# usbasp.net
KiCad netlist of a schematic drawn in EAGLE
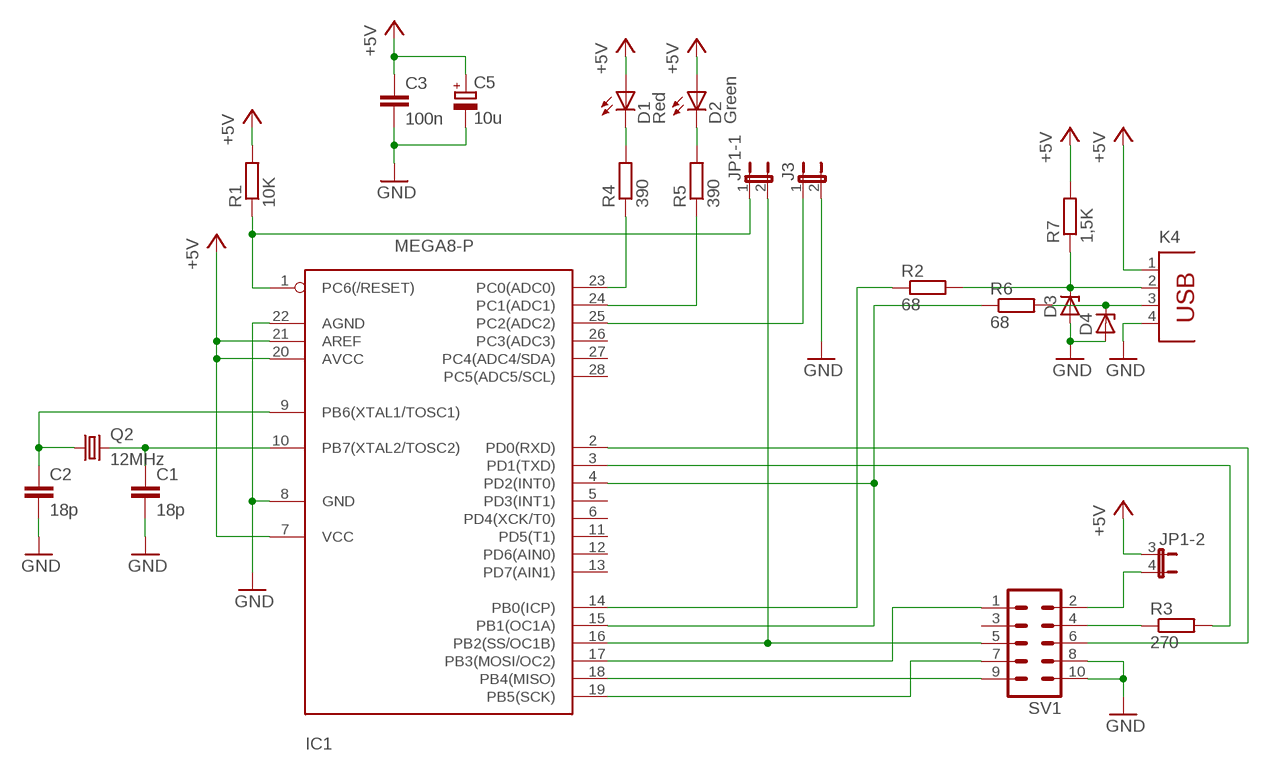
[diagram p0: schematic, sheet 1]

(export (version "E")
  (design (tool "Eeschema 10.0.6"))
  (components
    (comp (ref "C1")
      (value "18p")
      (footprint "eagle-import:C025-024X044")
      (libsource (lib "eagle-import") (part "C-EU025-024X044"))
    )
    (comp (ref "C2")
      (value "18p")
      (footprint "eagle-import:C025-024X044")
      (libsource (lib "eagle-import") (part "C-EU025-024X044"))
    )
    (comp (ref "C3")
      (value "100n")
      (footprint "eagle-import:C7.5B3")
      (libsource (lib "eagle-import") (part "C7.5/3"))
    )
    (comp (ref "C5")
      (value "10u")
      (footprint "eagle-import:E2,5-5")
      (libsource (lib "eagle-import") (part "CPOL-EUE2.5-5"))
    )
    (comp (ref "D1")
      (value "Red")
      (footprint "eagle-import:LED5MM")
      (libsource (lib "eagle-import") (part "LED5MM"))
    )
    (comp (ref "D2")
      (value "Green")
      (footprint "eagle-import:LED5MM")
      (libsource (lib "eagle-import") (part "LED5MM"))
    )
    (comp (ref "D3")
      (value "ZENER-DIODEZD-5")
      (footprint "eagle-import:ZDIO-5")
      (libsource (lib "eagle-import") (part "ZENER-DIODEZD-5"))
    )
    (comp (ref "D4")
      (value "ZENER-DIODEZD-2.5")
      (footprint "eagle-import:ZDIO-2.5")
      (libsource (lib "eagle-import") (part "ZENER-DIODEZD-2.5"))
    )
    (comp (ref "IC1")
      (value "MEGA8-P")
      (footprint "eagle-import:DIL28-3")
      (libsource (lib "eagle-import") (part "MEGA8-P"))
    )
    (comp (ref "J3")
      (value "JP1E")
      (footprint "eagle-import:JP1")
      (libsource (lib "eagle-import") (part "JP1E"))
    )
    (comp (ref "JP1")
      (value "JP2QE")
      (footprint "eagle-import:JP2Q")
      (libsource (lib "eagle-import") (part "JP2QE"))
    )
    (comp (ref "K4")
      (value "PN87520")
      (footprint "eagle-import:PN87520")
      (libsource (lib "eagle-import") (part "PN87520"))
    )
    (comp (ref "Q2")
      (value "12MHz")
      (footprint "eagle-import:HC49_S")
      (libsource (lib "eagle-import") (part "CRYTALHC49S"))
    )
    (comp (ref "R1")
      (value "10K")
      (footprint "eagle-import:0207_10")
      (libsource (lib "eagle-import") (part "R-EU_0207/10"))
    )
    (comp (ref "R2")
      (value "68")
      (footprint "eagle-import:0207_10")
      (libsource (lib "eagle-import") (part "R-EU_0207/10"))
    )
    (comp (ref "R3")
      (value "270")
      (footprint "eagle-import:0207_10")
      (libsource (lib "eagle-import") (part "R-EU_0207/10"))
    )
    (comp (ref "R4")
      (value "390")
      (footprint "eagle-import:0207_10")
      (libsource (lib "eagle-import") (part "R-EU_0207/10"))
    )
    (comp (ref "R5")
      (value "390")
      (footprint "eagle-import:0207_10")
      (libsource (lib "eagle-import") (part "R-EU_0207/10"))
    )
    (comp (ref "R6")
      (value "68")
      (footprint "eagle-import:0207_10")
      (libsource (lib "eagle-import") (part "R-EU_0207/10"))
    )
    (comp (ref "R7")
      (value "1,5K")
      (footprint "eagle-import:0207_10")
      (libsource (lib "eagle-import") (part "R-EU_0207/10"))
    )
    (comp (ref "SV1")
      (value "ML10")
      (footprint "eagle-import:ML10")
      (libsource (lib "eagle-import") (part "ML10"))
    )
  )
  (nets
    (net (code "1") (name "+5V") (class "Default")
      (node (ref "C3") (pin "1") (pinfunction "1_1") (pintype "passive"))
      (node (ref "C5") (pin "+") (pinfunction "+_+") (pintype "passive"))
      (node (ref "D1") (pin "A") (pinfunction "A_A") (pintype "passive"))
      (node (ref "D2") (pin "A") (pinfunction "A_A") (pintype "passive"))
      (node (ref "IC1") (pin "20") (pinfunction "AVCC_20") (pintype "bidirectional"))
      (node (ref "IC1") (pin "21") (pinfunction "AREF_21") (pintype "bidirectional"))
      (node (ref "IC1") (pin "7") (pinfunction "VCC_7") (pintype "bidirectional"))
      (node (ref "JP1") (pin "3") (pinfunction "1_3") (pintype "passive"))
      (node (ref "K4") (pin "1") (pinfunction "1_1") (pintype "passive"))
      (node (ref "R1") (pin "2") (pinfunction "2_2") (pintype "passive"))
      (node (ref "R7") (pin "2") (pinfunction "2_2") (pintype "passive"))
    )
    (net (code "2") (name "GND") (class "Default")
      (node (ref "C1") (pin "2") (pinfunction "2_2") (pintype "passive"))
      (node (ref "C2") (pin "2") (pinfunction "2_2") (pintype "passive"))
      (node (ref "C3") (pin "2") (pinfunction "2_2") (pintype "passive"))
      (node (ref "C5") (pin "-") (pinfunction "-_-") (pintype "passive"))
      (node (ref "D3") (pin "A") (pinfunction "A_A") (pintype "passive"))
      (node (ref "D4") (pin "A") (pinfunction "A_A") (pintype "passive"))
      (node (ref "IC1") (pin "22") (pinfunction "AGND_22") (pintype "bidirectional"))
      (node (ref "IC1") (pin "8") (pinfunction "GND_8") (pintype "bidirectional"))
      (node (ref "J3") (pin "2") (pinfunction "2_2") (pintype "passive"))
      (node (ref "K4") (pin "4") (pinfunction "4_4") (pintype "passive"))
      (node (ref "SV1") (pin "10") (pinfunction "10_10") (pintype "passive"))
      (node (ref "SV1") (pin "8") (pinfunction "8_8") (pintype "passive"))
    )
    (net (code "3") (name "Net-(D1-C)") (class "Default")
      (node (ref "D1") (pin "K") (pinfunction "C_K") (pintype "passive"))
      (node (ref "R4") (pin "2") (pinfunction "2_2") (pintype "passive"))
    )
    (net (code "4") (name "Net-(D2-C)") (class "Default")
      (node (ref "D2") (pin "K") (pinfunction "C_K") (pintype "passive"))
      (node (ref "R5") (pin "2") (pinfunction "2_2") (pintype "passive"))
    )
    (net (code "5") (name "Net-(D3-PadC)") (class "Default")
      (node (ref "D3") (pin "C") (pinfunction "C_C") (pintype "passive"))
      (node (ref "K4") (pin "2") (pinfunction "2_2") (pintype "passive"))
      (node (ref "R2") (pin "2") (pinfunction "2_2") (pintype "passive"))
      (node (ref "R7") (pin "1") (pinfunction "1_1") (pintype "passive"))
    )
    (net (code "6") (name "Net-(D4-PadC)") (class "Default")
      (node (ref "D4") (pin "C") (pinfunction "C_C") (pintype "passive"))
      (node (ref "K4") (pin "3") (pinfunction "3_3") (pintype "passive"))
      (node (ref "R6") (pin "2") (pinfunction "2_2") (pintype "passive"))
    )
    (net (code "7") (name "Net-(IC1-PB0(ICP))") (class "Default")
      (node (ref "IC1") (pin "14") (pinfunction "PB0(ICP)_14") (pintype "bidirectional"))
      (node (ref "R2") (pin "1") (pinfunction "1_1") (pintype "passive"))
    )
    (net (code "8") (name "Net-(IC1-PB1(OC1A))") (class "Default")
      (node (ref "IC1") (pin "15") (pinfunction "PB1(OC1A)_15") (pintype "bidirectional"))
      (node (ref "IC1") (pin "4") (pinfunction "PD2(INT0)_4") (pintype "bidirectional"))
      (node (ref "R6") (pin "1") (pinfunction "1_1") (pintype "passive"))
    )
    (net (code "9") (name "Net-(IC1-PB2(SS{slash}OC1B))") (class "Default")
      (node (ref "IC1") (pin "16") (pinfunction "PB2(SS/OC1B)_16") (pintype "bidirectional"))
      (node (ref "JP1") (pin "2") (pinfunction "2_2") (pintype "passive"))
      (node (ref "SV1") (pin "5") (pinfunction "5_5") (pintype "passive"))
    )
    (net (code "10") (name "Net-(IC1-PB3(MOSI{slash}OC2))") (class "Default")
      (node (ref "IC1") (pin "17") (pinfunction "PB3(MOSI/OC2)_17") (pintype "bidirectional"))
      (node (ref "SV1") (pin "1") (pinfunction "1_1") (pintype "passive"))
    )
    (net (code "11") (name "Net-(IC1-PB4(MISO))") (class "Default")
      (node (ref "IC1") (pin "18") (pinfunction "PB4(MISO)_18") (pintype "bidirectional"))
      (node (ref "SV1") (pin "9") (pinfunction "9_9") (pintype "passive"))
    )
    (net (code "12") (name "Net-(IC1-PB5(SCK))") (class "Default")
      (node (ref "IC1") (pin "19") (pinfunction "PB5(SCK)_19") (pintype "bidirectional"))
      (node (ref "SV1") (pin "7") (pinfunction "7_7") (pintype "passive"))
    )
    (net (code "13") (name "Net-(IC1-PB6(XTAL1{slash}TOSC1))") (class "Default")
      (node (ref "C2") (pin "1") (pinfunction "1_1") (pintype "passive"))
      (node (ref "IC1") (pin "9") (pinfunction "PB6(XTAL1/TOSC1)_9") (pintype "bidirectional"))
      (node (ref "Q2") (pin "1") (pinfunction "1_1") (pintype "passive"))
    )
    (net (code "14") (name "Net-(IC1-PB7(XTAL2{slash}TOSC2))") (class "Default")
      (node (ref "C1") (pin "1") (pinfunction "1_1") (pintype "passive"))
      (node (ref "IC1") (pin "10") (pinfunction "PB7(XTAL2/TOSC2)_10") (pintype "bidirectional"))
      (node (ref "Q2") (pin "2") (pinfunction "2_2") (pintype "passive"))
    )
    (net (code "15") (name "Net-(IC1-PC0(ADC0))") (class "Default")
      (node (ref "IC1") (pin "23") (pinfunction "PC0(ADC0)_23") (pintype "bidirectional"))
      (node (ref "R4") (pin "1") (pinfunction "1_1") (pintype "passive"))
    )
    (net (code "16") (name "Net-(IC1-PC1(ADC1))") (class "Default")
      (node (ref "IC1") (pin "24") (pinfunction "PC1(ADC1)_24") (pintype "bidirectional"))
      (node (ref "R5") (pin "1") (pinfunction "1_1") (pintype "passive"))
    )
    (net (code "17") (name "Net-(IC1-PC2(ADC2))") (class "Default")
      (node (ref "IC1") (pin "25") (pinfunction "PC2(ADC2)_25") (pintype "bidirectional"))
      (node (ref "J3") (pin "1") (pinfunction "1_1") (pintype "passive"))
    )
    (net (code "18") (name "Net-(IC1-PC6({slash}RESET))") (class "Default")
      (node (ref "IC1") (pin "1") (pinfunction "PC6(/RESET)_1") (pintype "bidirectional"))
      (node (ref "JP1") (pin "1") (pinfunction "1_1") (pintype "passive"))
      (node (ref "R1") (pin "1") (pinfunction "1_1") (pintype "passive"))
    )
    (net (code "19") (name "Net-(IC1-PD0(RXD))") (class "Default")
      (node (ref "IC1") (pin "2") (pinfunction "PD0(RXD)_2") (pintype "bidirectional"))
      (node (ref "SV1") (pin "6") (pinfunction "6_6") (pintype "passive"))
    )
    (net (code "20") (name "Net-(IC1-PD1(TXD))") (class "Default")
      (node (ref "IC1") (pin "3") (pinfunction "PD1(TXD)_3") (pintype "bidirectional"))
      (node (ref "R3") (pin "2") (pinfunction "2_2") (pintype "passive"))
    )
    (net (code "21") (name "Net-(JP1B-2)") (class "Default")
      (node (ref "JP1") (pin "4") (pinfunction "2_4") (pintype "passive"))
      (node (ref "SV1") (pin "2") (pinfunction "2_2") (pintype "passive"))
    )
    (net (code "22") (name "Net-(R3-Pad1)") (class "Default")
      (node (ref "R3") (pin "1") (pinfunction "1_1") (pintype "passive"))
      (node (ref "SV1") (pin "4") (pinfunction "4_4") (pintype "passive"))
    )
    (net (code "23") (name "unconnected-(IC1-PC3(ADC3)-Pad26)") (class "Default")
      (node (ref "IC1") (pin "26") (pinfunction "PC3(ADC3)_26") (pintype "bidirectional"))
    )
    (net (code "24") (name "unconnected-(IC1-PC4(ADC4{slash}SDA)-Pad27)") (class "Default")
      (node (ref "IC1") (pin "27") (pinfunction "PC4(ADC4/SDA)_27") (pintype "bidirectional"))
    )
    (net (code "25") (name "unconnected-(IC1-PC5(ADC5{slash}SCL)-Pad28)") (class "Default")
      (node (ref "IC1") (pin "28") (pinfunction "PC5(ADC5/SCL)_28") (pintype "bidirectional"))
    )
    (net (code "26") (name "unconnected-(IC1-PD3(INT1)-Pad5)") (class "Default")
      (node (ref "IC1") (pin "5") (pinfunction "PD3(INT1)_5") (pintype "bidirectional"))
    )
    (net (code "27") (name "unconnected-(IC1-PD4(XCK{slash}T0)-Pad6)") (class "Default")
      (node (ref "IC1") (pin "6") (pinfunction "PD4(XCK/T0)_6") (pintype "bidirectional"))
    )
    (net (code "28") (name "unconnected-(IC1-PD5(T1)-Pad11)") (class "Default")
      (node (ref "IC1") (pin "11") (pinfunction "PD5(T1)_11") (pintype "bidirectional"))
    )
    (net (code "29") (name "unconnected-(IC1-PD6(AIN0)-Pad12)") (class "Default")
      (node (ref "IC1") (pin "12") (pinfunction "PD6(AIN0)_12") (pintype "bidirectional"))
    )
    (net (code "30") (name "unconnected-(IC1-PD7(AIN1)-Pad13)") (class "Default")
      (node (ref "IC1") (pin "13") (pinfunction "PD7(AIN1)_13") (pintype "bidirectional"))
    )
    (net (code "31") (name "unconnected-(SV1-Pad3)") (class "Default")
      (node (ref "SV1") (pin "3") (pinfunction "3_3") (pintype "passive"))
    )
  )
)
